# MEMs_Breakout_Board.net
KiCad netlist of a schematic drawn in Altium Designer
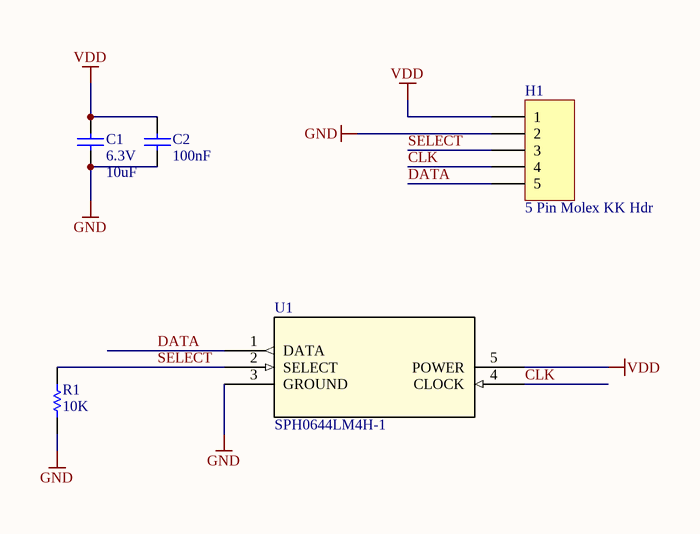
[diagram p0: MEMs_Breakout_Board.SchDoc]

(export (version "E")
  (design (tool "Eeschema 10.0.6"))
  (components
    (comp (ref "C1")
      (value "10uF")
      (footprint "CAPC1608L")
      (description "CAP CER 10UF X5R +-20% 6V3 0603")
      (fields (field (name "VOLTAGE - RATED") "6.3V"))
      (libsource (lib "ECE AD19Components_19V1") (part "CC_10uF_0603"))
    )
    (comp (ref "C2")
      (value "100nF")
      (footprint "CAPC1608L")
      (description "CAP CER 100nF X7R +-10% 50V 0603")
      (libsource (lib "ECE AD19Components_19V1") (part "CC_100nF_0603"))
    )
    (comp (ref "H1")
      (value "5 Pin Molex KK Hdr")
      (footprint "MOLEX_KK_5_HDR")
      (description "CONN HEADER 5POS 2.54mm VERT_Thru Hole")
      (fields (field (name "MANUFACTURER") "Molex"))
      (libsource (lib "ECE AD19Components_19V1") (part "JA_MOLEX_KK_5POS"))
    )
    (comp (ref "R1")
      (value "10K")
      (footprint "RESC1608L")
      (description "RES 10.0K OHM 1/10W 5% 0603 SMD")
      (libsource (lib "ECE AD19Components_19V1") (part "RS_10K"))
    )
    (comp (ref "U1")
      (value "SPH0644LM4H-1")
      (footprint "SPH0644LM4H-1_KNO")
      (description "No Description Available")
      (fields (field (name "COPYRIGHT") "Copyright (C) 2018 Accelerated Designs. All rights reserved"))
      (libsource (lib "2021-05-03_12-37-38") (part "SPH0644LM4H-1"))
    )
  )
  (nets
    (net (code "1") (name "/CLK") (class "Default")
      (node (ref "H1") (pin "4") (pinfunction "4_4") (pintype "passive"))
      (node (ref "U1") (pin "4") (pinfunction "CLOCK_4") (pintype "input"))
    )
    (net (code "2") (name "/DATA") (class "Default")
      (node (ref "H1") (pin "5") (pinfunction "5_5") (pintype "passive"))
      (node (ref "U1") (pin "1") (pinfunction "DATA_1") (pintype "output"))
    )
    (net (code "3") (name "/SELECT") (class "Default")
      (node (ref "H1") (pin "3") (pinfunction "3_3") (pintype "passive"))
      (node (ref "R1") (pin "2") (pinfunction "2_2") (pintype "passive"))
      (node (ref "U1") (pin "2") (pinfunction "SELECT_2") (pintype "input"))
    )
    (net (code "4") (name "GND") (class "Default")
      (node (ref "C1") (pin "1") (pinfunction "1_1") (pintype "passive"))
      (node (ref "C2") (pin "1") (pinfunction "1_1") (pintype "passive"))
      (node (ref "H1") (pin "2") (pinfunction "2_2") (pintype "passive"))
      (node (ref "R1") (pin "1") (pinfunction "1_1") (pintype "passive"))
      (node (ref "U1") (pin "3") (pinfunction "GROUND_3") (pintype "passive"))
    )
    (net (code "5") (name "VDD") (class "Default")
      (node (ref "C1") (pin "2") (pinfunction "2_2") (pintype "passive"))
      (node (ref "C2") (pin "2") (pinfunction "2_2") (pintype "passive"))
      (node (ref "H1") (pin "1") (pinfunction "1_1") (pintype "passive"))
      (node (ref "U1") (pin "5") (pinfunction "POWER_5") (pintype "power_in"))
    )
  )
)
